# DC_DC_HBridge.net
KiCad netlist of a schematic drawn in Altium Designer
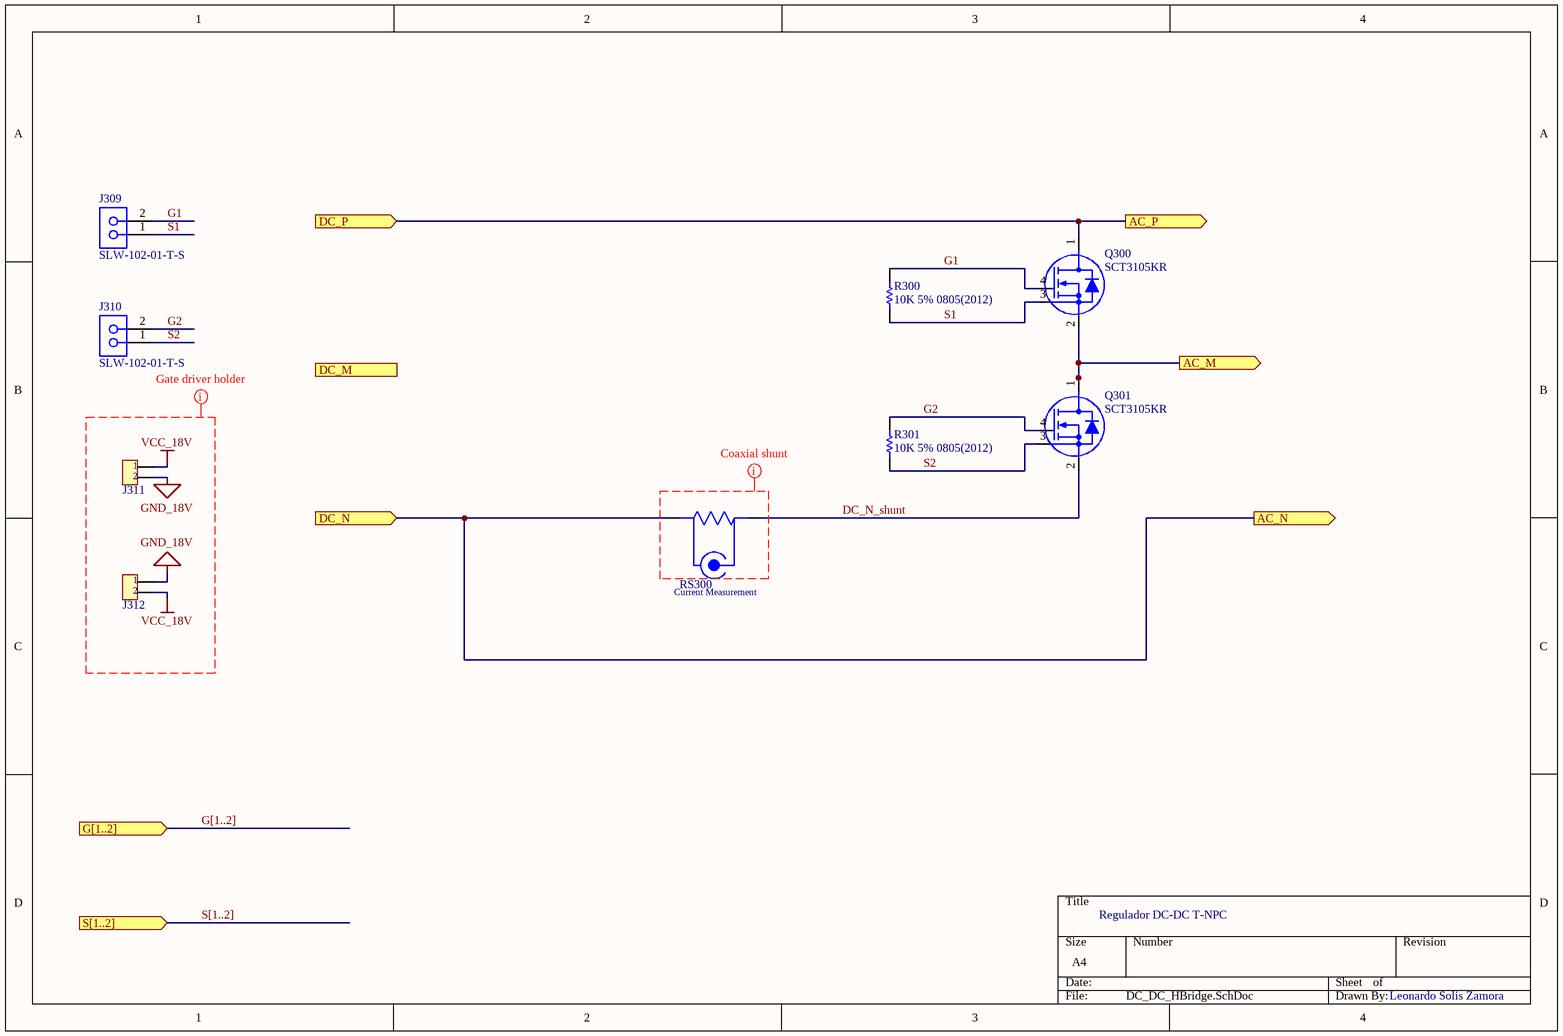
[diagram p0: DC_DC_HBridge.SchDoc]

(export (version "E")
  (design (tool "Eeschema 10.0.6"))
  (components
    (comp (ref "J309")
      (value "SLW-102-01-T-S")
      (footprint "SMTC-SLW-102-01-X-S")
      (fields (field (name "MANUFACTURER") "Samtec"))
      (libsource (lib "Altium Content Vault") (part "SMTC-SLW-102-01-X-S"))
    )
    (comp (ref "J310")
      (value "SLW-102-01-T-S")
      (footprint "SMTC-SLW-102-01-X-S")
      (fields (field (name "MANUFACTURER") "Samtec"))
      (libsource (lib "Altium Content Vault") (part "SMTC-SLW-102-01-X-S"))
    )
    (comp (ref "J311")
      (value "SSM-102-L-SV")
      (footprint "SSM-102-L-SV")
      (description "SAMTEC - SSM-102-L-SV - RECEPTACLE, 2.54MM, VERT, 2WAY")
      (fields (field (name "MANUFACTURER") "Samtec"))
      (libsource (lib "Altium_Library_POWERLAB") (part "SSM-102-L-SV"))
    )
    (comp (ref "J312")
      (value "SSM-102-L-SV")
      (footprint "SSM-102-L-SV")
      (description "SAMTEC - SSM-102-L-SV - RECEPTACLE, 2.54MM, VERT, 2WAY")
      (fields (field (name "MANUFACTURER") "Samtec"))
      (libsource (lib "Altium_Library_POWERLAB") (part "SSM-102-L-SV"))
    )
    (comp (ref "Q300")
      (value "SCT3105KR")
      (footprint "TO-247-4L_hsa")
      (description "N-channel SiC power MOSFET ROHM. Vdss 1200V, Rdson 105mOhm, Id 24A")
      (libsource (lib "Altium_Library_POWERLAB") (part "SCT3105KR"))
    )
    (comp (ref "Q301")
      (value "SCT3105KR")
      (footprint "TO-247-4L_hsa")
      (description "N-channel SiC power MOSFET ROHM. Vdss 1200V, Rdson 105mOhm, Id 24A")
      (libsource (lib "Altium_Library_POWERLAB") (part "SCT3105KR"))
    )
    (comp (ref "R300")
      (value "10K 5% 0805(2012)")
      (footprint "RESC0805(2012)_L")
      (description "10K 0.125W 5% 0805 (2012 Metric)  SMD")
      (fields (field (name "POWER") "0.125 W") (field (name "TOLERANCE") "5 %"))
      (libsource (lib "Altium Content Vault") (part "RES"))
    )
    (comp (ref "R301")
      (value "10K 5% 0805(2012)")
      (footprint "RESC0805(2012)_L")
      (description "10K 0.125W 5% 0805 (2012 Metric)  SMD")
      (fields (field (name "POWER") "0.125 W") (field (name "TOLERANCE") "5 %"))
      (libsource (lib "Altium Content Vault") (part "RES"))
    )
    (comp (ref "RS300")
      (value "SDN-414")
      (footprint "SDN-414")
      (description "Coaxial current shunt SDN-414 T&M (New)")
      (fields (field (name "MANUFACTURER") "Ohmite") (field (name "MANUFACTURER PART NUMBER") "WHE10RFET"))
      (libsource (lib "Altium_Library_POWERLAB") (part "SDN-414"))
    )
  )
  (nets
    (net (code "1") (name "/AC_M") (class "Default")
      (node (ref "Q300") (pin "2") (pinfunction "S_2") (pintype "passive"))
      (node (ref "Q301") (pin "1") (pinfunction "D_1") (pintype "passive"))
    )
    (net (code "2") (name "/AC_N") (class "Default")
      (node (ref "RS300") (pin "1") (pinfunction "-_1") (pintype "passive"))
    )
    (net (code "3") (name "/AC_P") (class "Default")
      (node (ref "Q300") (pin "1") (pinfunction "D_1") (pintype "passive"))
    )
    (net (code "5") (name "/DC_N_shunt") (class "Default")
      (node (ref "Q301") (pin "2") (pinfunction "S_2") (pintype "passive"))
      (node (ref "RS300") (pin "2") (pinfunction "+_2") (pintype "passive"))
    )
    (net (code "6") (name "/G1") (class "Default")
      (node (ref "J309") (pin "2") (pinfunction "2_2") (pintype "passive"))
      (node (ref "Q300") (pin "4") (pinfunction "G_4") (pintype "passive"))
      (node (ref "R300") (pin "1") (pinfunction "1_1") (pintype "passive"))
    )
    (net (code "7") (name "/G2") (class "Default")
      (node (ref "J310") (pin "2") (pinfunction "2_2") (pintype "passive"))
      (node (ref "Q301") (pin "4") (pinfunction "G_4") (pintype "passive"))
      (node (ref "R301") (pin "1") (pinfunction "1_1") (pintype "passive"))
    )
    (net (code "9") (name "/S1") (class "Default")
      (node (ref "J309") (pin "1") (pinfunction "1_1") (pintype "passive"))
      (node (ref "Q300") (pin "3") (pinfunction "KS_3") (pintype "passive"))
      (node (ref "R300") (pin "2") (pinfunction "2_2") (pintype "passive"))
    )
    (net (code "10") (name "/S2") (class "Default")
      (node (ref "J310") (pin "1") (pinfunction "1_1") (pintype "passive"))
      (node (ref "Q301") (pin "3") (pinfunction "KS_3") (pintype "passive"))
      (node (ref "R301") (pin "2") (pinfunction "2_2") (pintype "passive"))
    )
    (net (code "12") (name "GND_18V") (class "Default")
      (node (ref "J311") (pin "2") (pinfunction "2_2") (pintype "passive"))
      (node (ref "J312") (pin "1") (pinfunction "1_1") (pintype "passive"))
    )
    (net (code "13") (name "VCC_18V") (class "Default")
      (node (ref "J311") (pin "1") (pinfunction "1_1") (pintype "passive"))
      (node (ref "J312") (pin "2") (pinfunction "2_2") (pintype "passive"))
    )
  )
)
